# power_supply.net
KiCad netlist of a schematic drawn in Altium Designer
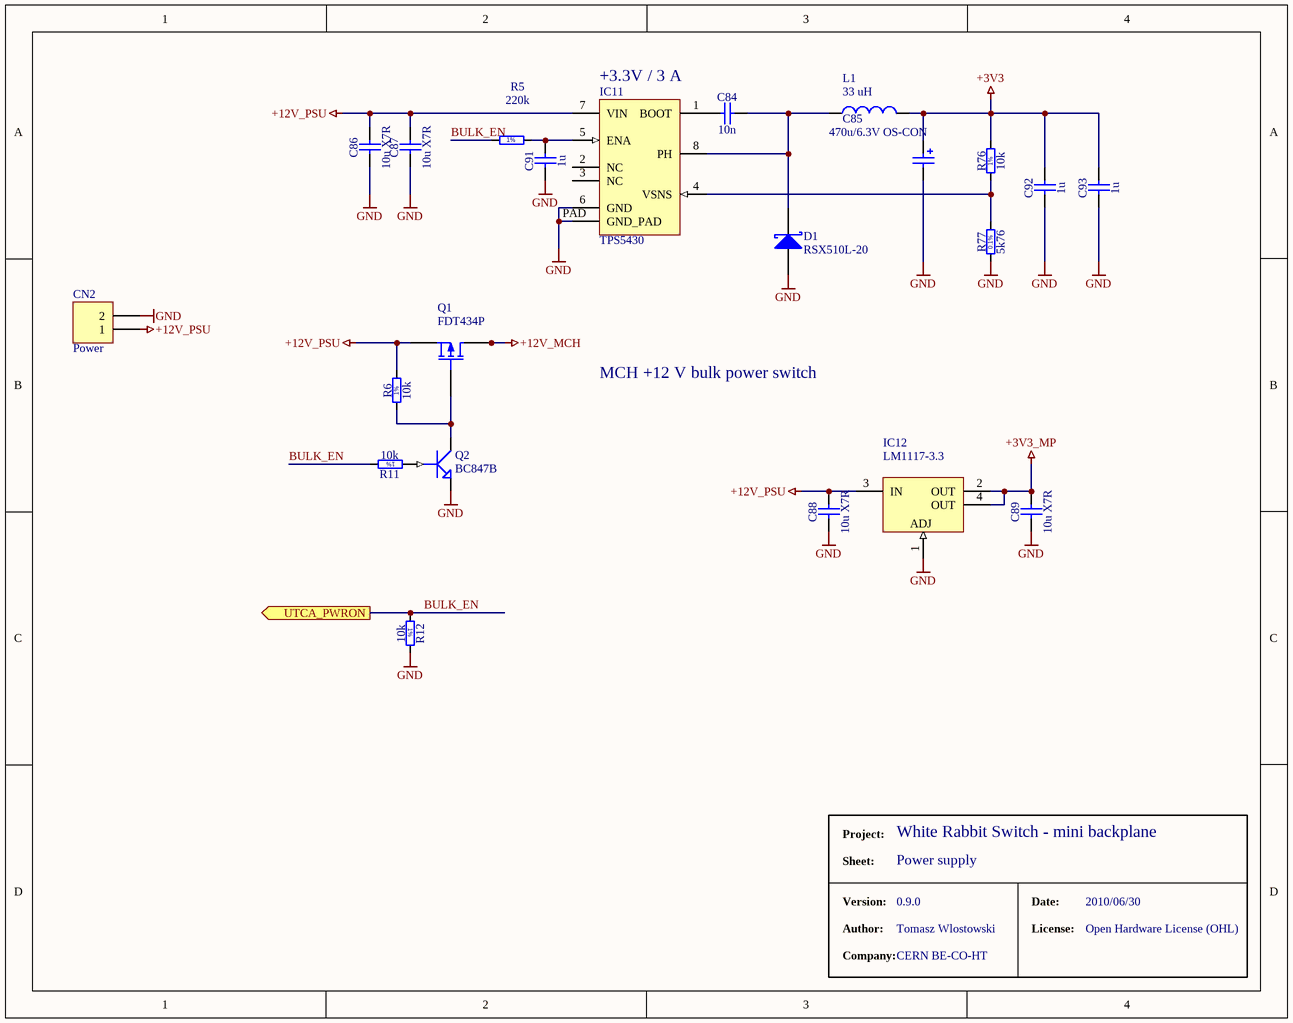
[diagram p0: power_supply.SchDoc]

(export (version "E")
  (design (tool "Eeschema 10.0.6"))
  (components
    (comp (ref "C84")
      (value "10n")
      (footprint "CAPC1608X87N")
      (description "Non-polarised capacitor")
      (fields
        (field (name "PART NUMBER") "CC0603_10NF_50V_10%_X7R")
        (field (name "VOLTAGE") "50V")
        (field (name "AUTHOR") "CERN DEM JLC")
      )
      (libsource (lib "Capacitors") (part "Capacitor - non polarized"))
    )
    (comp (ref "C85")
      (value "470u/6.3V OS-CON")
      (footprint "OSCON_F12")
      (description "Polarized Capacitor (Radial)")
      (fields (field (name "PUBLISHER") "Altium Limited"))
      (libsource (lib "wr_switch") (part "Cap Pol1"))
    )
    (comp (ref "C86")
      (value "10u X7R")
      (footprint "CAPC3216X140N")
      (description "Non-polarised capacitor")
      (fields
        (field (name "PART NUMBER") "CC1206_10UF_16V_10%_X7R")
        (field (name "VOLTAGE") "16V")
        (field (name "AUTHOR") "CERN DEM JLC")
      )
      (libsource (lib "Capacitors") (part "Capacitor - non polarized"))
    )
    (comp (ref "C87")
      (value "10u X7R")
      (footprint "CAPC3216X140N")
      (description "Non-polarised capacitor")
      (fields
        (field (name "PART NUMBER") "CC1206_10UF_16V_10%_X7R")
        (field (name "VOLTAGE") "16V")
        (field (name "AUTHOR") "CERN DEM JLC")
      )
      (libsource (lib "Capacitors") (part "Capacitor - non polarized"))
    )
    (comp (ref "C88")
      (value "10u X7R")
      (footprint "CAPC3216X140N")
      (description "Non-polarised capacitor")
      (fields
        (field (name "PART NUMBER") "CC1206_10UF_16V_10%_X7R")
        (field (name "VOLTAGE") "16V")
        (field (name "AUTHOR") "CERN DEM JLC")
      )
      (libsource (lib "Capacitors") (part "Capacitor - non polarized"))
    )
    (comp (ref "C89")
      (value "10u X7R")
      (footprint "CAPC3216X140N")
      (description "Non-polarised capacitor")
      (fields
        (field (name "PART NUMBER") "CC1206_10UF_16V_10%_X7R")
        (field (name "VOLTAGE") "16V")
        (field (name "AUTHOR") "CERN DEM JLC")
      )
      (libsource (lib "Capacitors") (part "Capacitor - non polarized"))
    )
    (comp (ref "C91")
      (value "1u")
      (footprint "CAPC1608X87N")
      (description "Non-polarised capacitor")
      (fields
        (field (name "PART NUMBER") "CC0603_1UF_16V_10%_X7R")
        (field (name "VOLTAGE") "16V")
        (field (name "AUTHOR") "CERN DEM JLC")
      )
      (libsource (lib "Capacitors") (part "Capacitor - non polarized"))
    )
    (comp (ref "C92")
      (value "1u")
      (footprint "CAPC3216X140N")
      (description "Non-polarised capacitor")
      (fields
        (field (name "PART NUMBER") "CC1206_1UF_16V_10%_X7R")
        (field (name "VOLTAGE") "16V")
        (field (name "AUTHOR") "CERN DEM JLC")
      )
      (libsource (lib "Capacitors") (part "Capacitor - non polarized"))
    )
    (comp (ref "C93")
      (value "1u")
      (footprint "CAPC3216X140N")
      (description "Non-polarised capacitor")
      (fields
        (field (name "PART NUMBER") "CC1206_1UF_16V_10%_X7R")
        (field (name "VOLTAGE") "16V")
        (field (name "AUTHOR") "CERN DEM JLC")
      )
      (libsource (lib "Capacitors") (part "Capacitor - non polarized"))
    )
    (comp (ref "CN2")
      (value "Power")
      (footprint "CON_3.96_2")
      (description "Header, 2-Pin")
      (fields (field (name "PUBLISHER") "Altium Limited"))
      (libsource (lib "Miscellaneous Connectors") (part "Header 2"))
    )
    (comp (ref "D1")
      (value "RSX510L-20")
      (footprint "CD4532-1812")
      (description "Schottky Diode")
      (fields (field (name "PUBLISHER") "Altium Limited"))
      (libsource (lib "wr_switch") (part "D Schottky"))
    )
    (comp (ref "IC11")
      (value "TPS5430")
      (footprint "SOIC127P600-8AL_POWERPAD")
      (description "Step-down switchmode converter")
      (libsource (lib "wr_switch") (part "TPS5430"))
    )
    (comp (ref "IC12")
      (value "LM1117-3.3")
      (footprint "SOT223-4L")
      (description "Three-Terminal Adjustable Output Positive Voltage Regulator")
      (fields (field (name "PUBLISHER") "Altium Limited"))
      (libsource (lib "wr_switch") (part "1117"))
    )
    (comp (ref "L1")
      (value "33 uH")
      (footprint "IND0943-B")
      (description "Inductor")
      (fields (field (name "PUBLISHER") "Altium Limited"))
      (libsource (lib "wr_switch") (part "Inductor"))
    )
    (comp (ref "Q1")
      (value "FDT434P")
      (footprint "SOT223-4L")
      (description "P-Channel MOSFET")
      (fields (field (name "PUBLISHER") "Altium Limited"))
      (libsource (lib "wr_switch") (part "Q_FDT434P"))
    )
    (comp (ref "Q2")
      (value "BC847B")
      (footprint "SOT-23")
      (description "Transistor")
      (libsource (lib "LIBRARY_SCH") (part "Q_BC847B"))
    )
    (comp (ref "R5")
      (value "220k")
      (footprint "RESC1608X55N")
      (description "Resistor - 1%")
      (fields
        (field (name "PART NUMBER") "R0603_220K_1%_0.1W_100PPM")
        (field (name "POWER") "0.1W")
        (field (name "AUTHOR") "CERN DEM JLC")
      )
      (libsource (lib "Resistors") (part "Resistor - 1%"))
    )
    (comp (ref "R6")
      (value "10k")
      (footprint "RESC1608X55N")
      (description "Resistor - 1%")
      (fields
        (field (name "PART NUMBER") "R0603_10K_1%_0.1W_100PPM")
        (field (name "POWER") "0.1W")
        (field (name "AUTHOR") "CERN DEM JLC")
      )
      (libsource (lib "Resistors") (part "Resistor - 1%"))
    )
    (comp (ref "R11")
      (value "10k")
      (footprint "RESC1608X55N")
      (description "Resistor - 1%")
      (fields
        (field (name "PART NUMBER") "R0603_10K_1%_0.1W_100PPM")
        (field (name "POWER") "0.1W")
        (field (name "AUTHOR") "CERN DEM JLC")
      )
      (libsource (lib "Resistors") (part "Resistor - 1%"))
    )
    (comp (ref "R12")
      (value "10k")
      (footprint "RESC1608X55N")
      (description "Resistor - 1%")
      (fields
        (field (name "PART NUMBER") "R0603_10K_1%_0.1W_100PPM")
        (field (name "POWER") "0.1W")
        (field (name "AUTHOR") "CERN DEM JLC")
      )
      (libsource (lib "Resistors") (part "Resistor - 1%"))
    )
    (comp (ref "R76")
      (value "10k")
      (footprint "RESC1608X55N")
      (description "Resistor - 1%")
      (fields
        (field (name "PART NUMBER") "R0603_10K_1%_0.1W_100PPM")
        (field (name "POWER") "0.1W")
        (field (name "AUTHOR") "CERN DEM JLC")
      )
      (libsource (lib "Resistors") (part "Resistor - 1%"))
    )
    (comp (ref "R77")
      (value "5k76")
      (footprint "RESC1608X55N")
      (description "Resistor - 0.1%")
      (fields
        (field (name "PART NUMBER") "R0603_5K76_0.1%_0.063W_10PPM")
        (field (name "POWER") "0.063W")
        (field (name "AUTHOR") "CERN DEM JLC")
      )
      (libsource (lib "Resistors") (part "Resistor - 0.1%"))
    )
  )
  (nets
    (net (code "1") (name "+3V3") (class "Default")
      (node (ref "C85") (pin "1") (pinfunction "1_1") (pintype "passive"))
      (node (ref "C92") (pin "2") (pinfunction "2_2") (pintype "passive"))
      (node (ref "C93") (pin "2") (pinfunction "2_2") (pintype "passive"))
      (node (ref "L1") (pin "2") (pinfunction "2_2") (pintype "passive"))
      (node (ref "R76") (pin "2") (pinfunction "2_2") (pintype "passive"))
    )
    (net (code "2") (name "+3V3_MP") (class "Default")
      (node (ref "C89") (pin "2") (pinfunction "2_2") (pintype "passive"))
      (node (ref "IC12") (pin "2") (pinfunction "OUT_2") (pintype "power_in"))
      (node (ref "IC12") (pin "4") (pinfunction "OUT_4") (pintype "power_in"))
    )
    (net (code "3") (name "+12V_MCH") (class "Default")
      (node (ref "Q1") (pin "2") (pinfunction "D_2") (pintype "passive"))
      (node (ref "Q1") (pin "4") (pinfunction "D_4") (pintype "passive"))
    )
    (net (code "4") (name "+12V_PSU") (class "Default")
      (node (ref "C86") (pin "2") (pinfunction "2_2") (pintype "passive"))
      (node (ref "C87") (pin "2") (pinfunction "2_2") (pintype "passive"))
      (node (ref "C88") (pin "2") (pinfunction "2_2") (pintype "passive"))
      (node (ref "CN2") (pin "1") (pinfunction "1_1") (pintype "passive"))
      (node (ref "IC11") (pin "7") (pinfunction "VIN_7") (pintype "power_in"))
      (node (ref "IC12") (pin "3") (pinfunction "IN_3") (pintype "power_in"))
      (node (ref "Q1") (pin "3") (pinfunction "S_3") (pintype "passive"))
      (node (ref "R6") (pin "2") (pinfunction "2_2") (pintype "passive"))
    )
    (net (code "5") (name "/BULK_EN") (class "Default")
      (node (ref "R11") (pin "2") (pinfunction "2_2") (pintype "passive"))
      (node (ref "R12") (pin "1") (pinfunction "1_1") (pintype "passive"))
      (node (ref "R5") (pin "1") (pinfunction "1_1") (pintype "passive"))
    )
    (net (code "6") (name "GND") (class "Default")
      (node (ref "C85") (pin "2") (pinfunction "2_2") (pintype "passive"))
      (node (ref "C86") (pin "1") (pinfunction "1_1") (pintype "passive"))
      (node (ref "C87") (pin "1") (pinfunction "1_1") (pintype "passive"))
      (node (ref "C88") (pin "1") (pinfunction "1_1") (pintype "passive"))
      (node (ref "C89") (pin "1") (pinfunction "1_1") (pintype "passive"))
      (node (ref "C91") (pin "1") (pinfunction "1_1") (pintype "passive"))
      (node (ref "C92") (pin "1") (pinfunction "1_1") (pintype "passive"))
      (node (ref "C93") (pin "1") (pinfunction "1_1") (pintype "passive"))
      (node (ref "CN2") (pin "2") (pinfunction "2_2") (pintype "passive"))
      (node (ref "D1") (pin "1") (pinfunction "A_1") (pintype "passive"))
      (node (ref "IC11") (pin "6") (pinfunction "GND_6") (pintype "power_in"))
      (node (ref "IC11") (pin "PAD") (pinfunction "GND_PAD_PAD") (pintype "power_in"))
      (node (ref "IC12") (pin "1") (pinfunction "ADJ_1") (pintype "input"))
      (node (ref "Q2") (pin "2") (pinfunction "E_2") (pintype "passive"))
      (node (ref "R12") (pin "2") (pinfunction "2_2") (pintype "passive"))
      (node (ref "R77") (pin "1") (pinfunction "1_1") (pintype "passive"))
    )
    (net (code "7") (name "Net-(D1-K)") (class "Default")
      (node (ref "C84") (pin "2") (pinfunction "2_2") (pintype "passive"))
      (node (ref "D1") (pin "2") (pinfunction "K_2") (pintype "passive"))
      (node (ref "IC11") (pin "8") (pinfunction "PH_8") (pintype "power_in"))
      (node (ref "L1") (pin "1") (pinfunction "1_1") (pintype "passive"))
    )
    (net (code "8") (name "Net-(IC11-BOOT)") (class "Default")
      (node (ref "C84") (pin "1") (pinfunction "1_1") (pintype "passive"))
      (node (ref "IC11") (pin "1") (pinfunction "BOOT_1") (pintype "passive"))
    )
    (net (code "9") (name "Net-(IC11-ENA)") (class "Default")
      (node (ref "C91") (pin "2") (pinfunction "2_2") (pintype "passive"))
      (node (ref "IC11") (pin "5") (pinfunction "ENA_5") (pintype "input"))
      (node (ref "R5") (pin "2") (pinfunction "2_2") (pintype "passive"))
    )
    (net (code "10") (name "Net-(IC11-VSNS)") (class "Default")
      (node (ref "IC11") (pin "4") (pinfunction "VSNS_4") (pintype "input"))
      (node (ref "R76") (pin "1") (pinfunction "1_1") (pintype "passive"))
      (node (ref "R77") (pin "2") (pinfunction "2_2") (pintype "passive"))
    )
    (net (code "11") (name "Net-(Q1-G)") (class "Default")
      (node (ref "Q1") (pin "1") (pinfunction "G_1") (pintype "passive"))
      (node (ref "Q2") (pin "3") (pinfunction "C_3") (pintype "passive"))
      (node (ref "R6") (pin "1") (pinfunction "1_1") (pintype "passive"))
    )
    (net (code "12") (name "Net-(Q2-B)") (class "Default")
      (node (ref "Q2") (pin "1") (pinfunction "B_1") (pintype "input"))
      (node (ref "R11") (pin "1") (pinfunction "1_1") (pintype "passive"))
    )
    (net (code "13") (name "unconnected-(IC11-NC-Pad2)") (class "Default")
      (node (ref "IC11") (pin "2") (pinfunction "NC_2") (pintype "passive"))
    )
    (net (code "14") (name "unconnected-(IC11-NC-Pad3)") (class "Default")
      (node (ref "IC11") (pin "3") (pinfunction "NC_3") (pintype "passive"))
    )
  )
)
